# design.net
KiCad netlist of a schematic drawn in Altium Designer
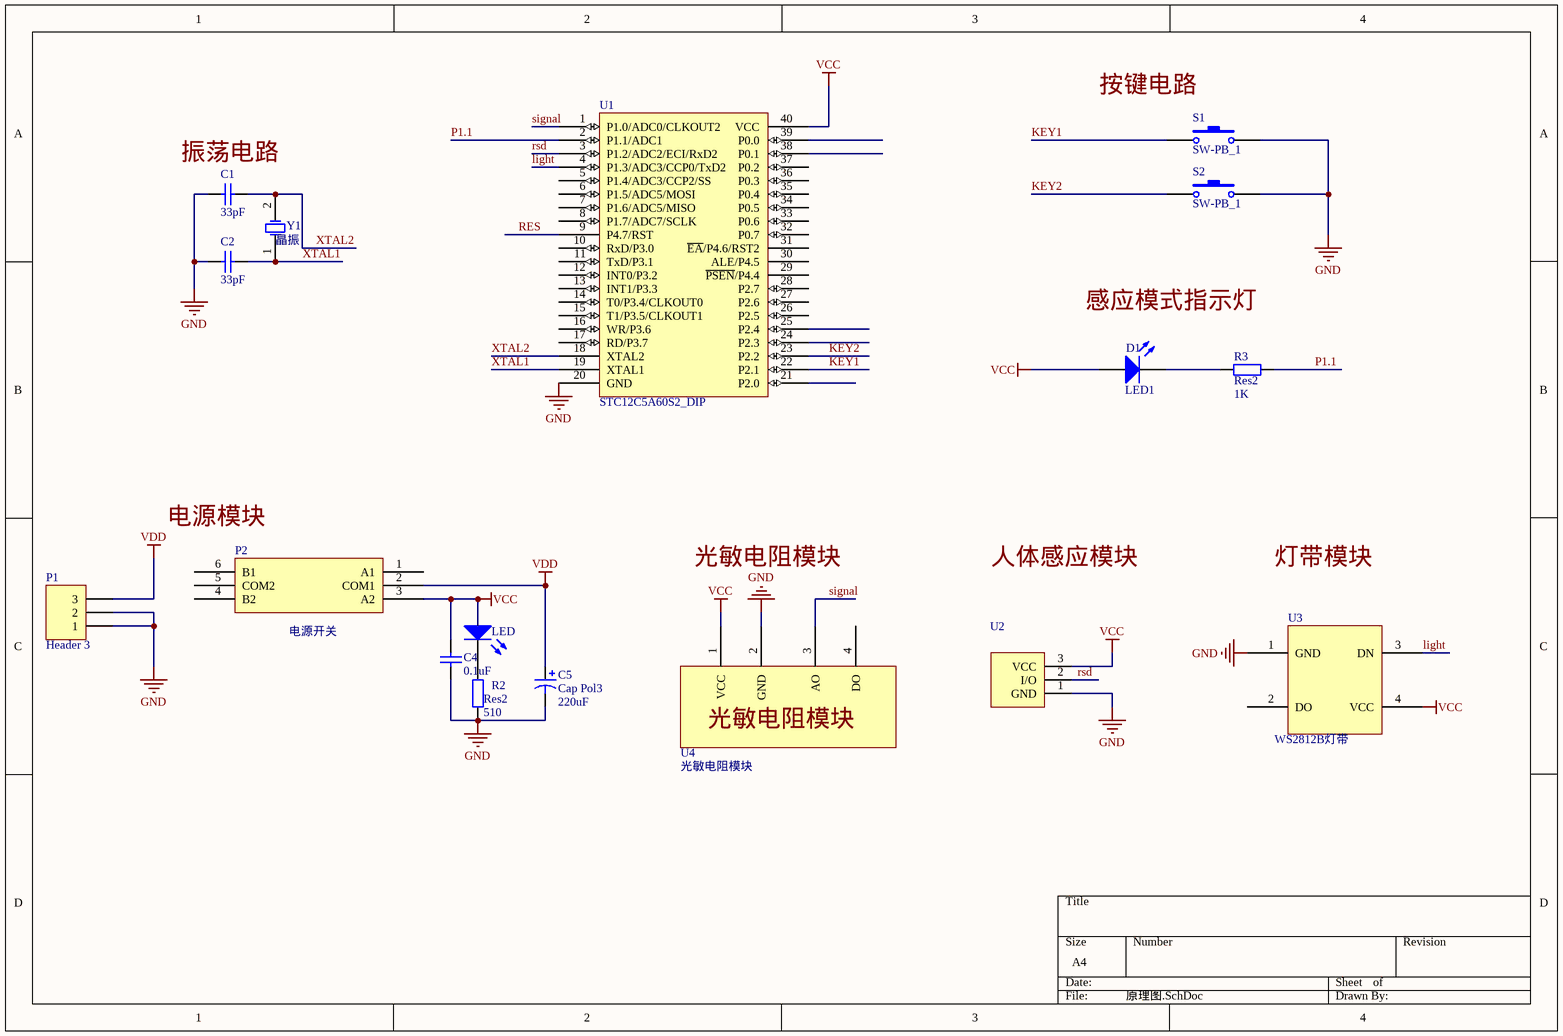
[diagram p0: 原理图.SchDoc]

(export (version "E")
  (design (tool "Eeschema 10.0.6"))
  (components
    (comp (ref "C1")
      (value "33pF")
      (footprint "Capacitor-Disk-Middle")
      (description "CBB聚乙烯薄膜电容")
      (fields
        (field (name "VOLTAGE") "63V")
        (field (name "Comment") "Cap Nicklon")
        (field (name "PUBLISHER") "Altium Limited")
      )
      (libsource (lib "02 Miscellaneous_Devices_ZSF_Library") (part "Cap Nicklon"))
    )
    (comp (ref "C2")
      (value "33pF")
      (footprint "Capacitor-Disk-Middle")
      (description "CBB聚乙烯薄膜电容")
      (fields
        (field (name "VOLTAGE") "63V")
        (field (name "Comment") "Cap Nicklon")
        (field (name "PUBLISHER") "Altium Limited")
      )
      (libsource (lib "02 Miscellaneous_Devices_ZSF_Library") (part "Cap Nicklon"))
    )
    (comp (ref "C4")
      (value "0.1uF")
      (footprint "Capacitor-Disk-Middle")
      (description "CBB聚乙烯薄膜电容")
      (fields
        (field (name "VOLTAGE") "63V")
        (field (name "Comment") "Cap Nicklon")
        (field (name "PUBLISHER") "Altium Limited")
      )
      (libsource (lib "02 Miscellaneous_Devices_ZSF_Library") (part "Cap Nicklon"))
    )
    (comp (ref "C5")
      (value "Cap Pol3")
      (footprint "ED4")
      (description "Polarized Capacitor (Surface Mount)")
      (fields (field (name "ALTIUM_VALUE") "220uF") (field (name "PUBLISHER") "Altium Limited"))
      (libsource (lib "Miscellaneous Devices") (part "Cap Pol3"))
    )
    (comp (ref "D1")
      (value "LED1")
      (footprint "CLED3216-1206")
      (description "Typical INFRARED GaAs LED")
      (fields (field (name "PUBLISHER") "Altium Limited"))
      (libsource (lib "Miscellaneous Devices") (part "LED0"))
    )
    (comp (ref "LED")
      (value "LED Chip")
      (footprint "CLED3216-1206")
      (description "Typical Chip LED")
      (fields (field (name "PUBLISHER") "Altium Limited"))
      (libsource (lib "03-EButterflyIntegratedLibrary") (part "LED Chip"))
    )
    (comp (ref "P1")
      (value "Header 3")
      (footprint "HT396K-3")
      (description "Header, 3-Pin")
      (fields (field (name "PUBLISHER") "Altium Limited"))
      (libsource (lib "01 Connect_IntegratedLibrary") (part "Header 3"))
    )
    (comp (ref "P2") (value "电源开关") (footprint "HDR2X3_CEN") (libsource (lib "stc12") (part "电源开关")))
    (comp (ref "R2")
      (value "Res2")
      (footprint "AXIAL-0.4")
      (description "Resistor")
      (fields (field (name "ALTIUM_VALUE") "510") (field (name "PUBLISHER") "Altium Limited"))
      (libsource (lib "") (part "Res2_1"))
    )
    (comp (ref "R3")
      (value "Res2")
      (footprint "AXIAL-0.4")
      (description "Resistor")
      (fields (field (name "ALTIUM_VALUE") "1K") (field (name "PUBLISHER") "Altium Limited"))
      (libsource (lib "Miscellaneous Devices") (part "Res2"))
    )
    (comp (ref "S1")
      (value "SW-PB_1")
      (footprint "BUTTON_6*6")
      (description "Switch")
      (fields (field (name "PUBLISHER") "Altium Limited"))
      (libsource (lib "02 Miscellaneous_Devices_ZSF_Library") (part "SW-PB_1"))
    )
    (comp (ref "S2")
      (value "SW-PB_1")
      (footprint "BUTTON_6*6")
      (description "Switch")
      (fields (field (name "PUBLISHER") "Altium Limited"))
      (libsource (lib "02 Miscellaneous_Devices_ZSF_Library") (part "SW-PB_1"))
    )
    (comp (ref "U1")
      (value "STC12C5A60S2_DIP")
      (footprint "dip40 - 紧缩座")
      (libsource (lib "02 Miscellaneous_Devices_ZSF_Library") (part "STC12C5A60S2_DIP"))
    )
    (comp (ref "U2") (value "人体感应模块") (footprint "人体感应模块") (libsource (lib "常用集成库(1)") (part "DS18B20")))
    (comp (ref "U3") (value "WS2812B灯带") (footprint "灯带模块") (libsource (lib "stc12") (part "WS2812B")))
    (comp (ref "U4") (value "光敏电阻模块") (footprint "光敏电阻模块") (libsource (lib "stc12") (part "光敏电阻模块")))
    (comp (ref "Y1")
      (value "晶振")
      (footprint "cry卧式")
      (description "直插晶振11.05292/12/16/24/MHz")
      (libsource (lib "02 Miscellaneous_Devices_ZSF_Library") (part "Crystal 11.05292/12/16/24/MHz"))
    )
  )
  (nets
    (net (code "1") (name "/KEY1") (class "Default")
      (node (ref "S1") (pin "1") (pinfunction "1_1") (pintype "passive"))
      (node (ref "U1") (pin "22") (pinfunction "P2.1_22") (pintype "bidirectional"))
    )
    (net (code "2") (name "/KEY2") (class "Default")
      (node (ref "S2") (pin "1") (pinfunction "1_1") (pintype "passive"))
      (node (ref "U1") (pin "23") (pinfunction "P2.2_23") (pintype "bidirectional"))
    )
    (net (code "3") (name "/P1.1") (class "Default")
      (node (ref "R3") (pin "2") (pinfunction "2_2") (pintype "passive"))
      (node (ref "U1") (pin "2") (pinfunction "P1.1/ADC1_2") (pintype "bidirectional"))
    )
    (net (code "4") (name "/RES") (class "Default")
      (node (ref "U1") (pin "9") (pinfunction "P4.7/RST_9") (pintype "passive"))
    )
    (net (code "5") (name "/XTAL1") (class "Default")
      (node (ref "C2") (pin "2") (pinfunction "2_2") (pintype "passive"))
      (node (ref "U1") (pin "19") (pinfunction "XTAL1_19") (pintype "passive"))
      (node (ref "Y1") (pin "1") (pinfunction "OSC1_1") (pintype "passive"))
    )
    (net (code "6") (name "/XTAL2") (class "Default")
      (node (ref "C1") (pin "2") (pinfunction "2_2") (pintype "passive"))
      (node (ref "U1") (pin "18") (pinfunction "XTAL2_18") (pintype "passive"))
      (node (ref "Y1") (pin "2") (pinfunction "OSC2_2") (pintype "passive"))
    )
    (net (code "7") (name "/light") (class "Default")
      (node (ref "U1") (pin "4") (pinfunction "P1.3/ADC3/CCP0/TxD2_4") (pintype "bidirectional"))
      (node (ref "U3") (pin "3") (pinfunction "DN_3") (pintype "passive"))
    )
    (net (code "8") (name "/rsd") (class "Default")
      (node (ref "U1") (pin "3") (pinfunction "P1.2/ADC2/ECI/RxD2_3") (pintype "bidirectional"))
      (node (ref "U2") (pin "2") (pinfunction "I/O_2") (pintype "passive"))
    )
    (net (code "9") (name "/signal") (class "Default")
      (node (ref "U1") (pin "1") (pinfunction "P1.0/ADC0/CLKOUT2_1") (pintype "bidirectional"))
      (node (ref "U4") (pin "3") (pinfunction "AO_3") (pintype "passive"))
    )
    (net (code "10") (name "GND") (class "Default")
      (node (ref "C1") (pin "1") (pinfunction "1_1") (pintype "passive"))
      (node (ref "C2") (pin "1") (pinfunction "1_1") (pintype "passive"))
      (node (ref "C4") (pin "1") (pinfunction "1_1") (pintype "passive"))
      (node (ref "C5") (pin "2") (pinfunction "2_2") (pintype "passive"))
      (node (ref "P1") (pin "1") (pinfunction "1_1") (pintype "passive"))
      (node (ref "P1") (pin "2") (pinfunction "2_2") (pintype "passive"))
      (node (ref "R2") (pin "1") (pinfunction "1_1") (pintype "passive"))
      (node (ref "S1") (pin "2") (pinfunction "2_2") (pintype "passive"))
      (node (ref "S2") (pin "2") (pinfunction "2_2") (pintype "passive"))
      (node (ref "U1") (pin "20") (pinfunction "GND_20") (pintype "power_in"))
      (node (ref "U2") (pin "1") (pinfunction "GND_1") (pintype "passive"))
      (node (ref "U3") (pin "1") (pinfunction "GND_1") (pintype "passive"))
      (node (ref "U4") (pin "2") (pinfunction "GND_2") (pintype "passive"))
    )
    (net (code "11") (name "Net-(D1-K)") (class "Default")
      (node (ref "D1") (pin "2") (pinfunction "K_2") (pintype "passive"))
      (node (ref "R3") (pin "1") (pinfunction "1_1") (pintype "passive"))
    )
    (net (code "12") (name "Net-(LED-K)") (class "Default")
      (node (ref "LED") (pin "2") (pinfunction "K_2") (pintype "passive"))
      (node (ref "R2") (pin "2") (pinfunction "2_2") (pintype "passive"))
    )
    (net (code "13") (name "VCC") (class "Default")
      (node (ref "C4") (pin "2") (pinfunction "2_2") (pintype "passive"))
      (node (ref "D1") (pin "1") (pinfunction "A_1") (pintype "passive"))
      (node (ref "LED") (pin "1") (pinfunction "A_1") (pintype "passive"))
      (node (ref "P2") (pin "3") (pinfunction "A2_3") (pintype "passive"))
      (node (ref "U1") (pin "40") (pinfunction "VCC_40") (pintype "power_in"))
      (node (ref "U2") (pin "3") (pinfunction "VCC_3") (pintype "passive"))
      (node (ref "U3") (pin "4") (pinfunction "VCC_4") (pintype "passive"))
      (node (ref "U4") (pin "1") (pinfunction "VCC_1") (pintype "passive"))
    )
    (net (code "14") (name "VDD") (class "Default")
      (node (ref "C5") (pin "1") (pinfunction "1_1") (pintype "passive"))
      (node (ref "P1") (pin "3") (pinfunction "3_3") (pintype "passive"))
      (node (ref "P2") (pin "2") (pinfunction "COM1_2") (pintype "passive"))
    )
    (net (code "15") (name "unconnected-(P2-A1-Pad1)") (class "Default")
      (node (ref "P2") (pin "1") (pinfunction "A1_1") (pintype "passive"))
    )
    (net (code "16") (name "unconnected-(P2-B1-Pad6)") (class "Default")
      (node (ref "P2") (pin "6") (pinfunction "B1_6") (pintype "passive"))
    )
    (net (code "17") (name "unconnected-(P2-B2-Pad4)") (class "Default")
      (node (ref "P2") (pin "4") (pinfunction "B2_4") (pintype "passive"))
    )
    (net (code "18") (name "unconnected-(P2-COM2-Pad5)") (class "Default")
      (node (ref "P2") (pin "5") (pinfunction "COM2_5") (pintype "passive"))
    )
    (net (code "19") (name "unconnected-(U1-ALE{slash}P4.5-Pad30)") (class "Default")
      (node (ref "U1") (pin "30") (pinfunction "ALE/P4.5_30") (pintype "passive"))
    )
    (net (code "20") (name "unconnected-(U1-INT0{slash}P3.2-Pad12)") (class "Default")
      (node (ref "U1") (pin "12") (pinfunction "INT0/P3.2_12") (pintype "bidirectional"))
    )
    (net (code "21") (name "unconnected-(U1-INT1{slash}P3.3-Pad13)") (class "Default")
      (node (ref "U1") (pin "13") (pinfunction "INT1/P3.3_13") (pintype "bidirectional"))
    )
    (net (code "22") (name "unconnected-(U1-P0.0-Pad39)") (class "Default")
      (node (ref "U1") (pin "39") (pinfunction "P0.0_39") (pintype "bidirectional"))
    )
    (net (code "23") (name "unconnected-(U1-P0.1-Pad38)") (class "Default")
      (node (ref "U1") (pin "38") (pinfunction "P0.1_38") (pintype "bidirectional"))
    )
    (net (code "24") (name "unconnected-(U1-P0.2-Pad37)") (class "Default")
      (node (ref "U1") (pin "37") (pinfunction "P0.2_37") (pintype "bidirectional"))
    )
    (net (code "25") (name "unconnected-(U1-P0.3-Pad36)") (class "Default")
      (node (ref "U1") (pin "36") (pinfunction "P0.3_36") (pintype "bidirectional"))
    )
    (net (code "26") (name "unconnected-(U1-P0.4-Pad35)") (class "Default")
      (node (ref "U1") (pin "35") (pinfunction "P0.4_35") (pintype "bidirectional"))
    )
    (net (code "27") (name "unconnected-(U1-P0.5-Pad34)") (class "Default")
      (node (ref "U1") (pin "34") (pinfunction "P0.5_34") (pintype "bidirectional"))
    )
    (net (code "28") (name "unconnected-(U1-P0.6-Pad33)") (class "Default")
      (node (ref "U1") (pin "33") (pinfunction "P0.6_33") (pintype "bidirectional"))
    )
    (net (code "29") (name "unconnected-(U1-P0.7-Pad32)") (class "Default")
      (node (ref "U1") (pin "32") (pinfunction "P0.7_32") (pintype "bidirectional"))
    )
    (net (code "30") (name "unconnected-(U1-P1.4{slash}ADC3{slash}CCP2{slash}SS-Pad5)") (class "Default")
      (node (ref "U1") (pin "5") (pinfunction "P1.4/ADC3/CCP2/SS_5") (pintype "bidirectional"))
    )
    (net (code "31") (name "unconnected-(U1-P1.5{slash}ADC5{slash}MOSI-Pad6)") (class "Default")
      (node (ref "U1") (pin "6") (pinfunction "P1.5/ADC5/MOSI_6") (pintype "bidirectional"))
    )
    (net (code "32") (name "unconnected-(U1-P1.6{slash}ADC5{slash}MISO-Pad7)") (class "Default")
      (node (ref "U1") (pin "7") (pinfunction "P1.6/ADC5/MISO_7") (pintype "bidirectional"))
    )
    (net (code "33") (name "unconnected-(U1-P1.7{slash}ADC7{slash}SCLK-Pad8)") (class "Default")
      (node (ref "U1") (pin "8") (pinfunction "P1.7/ADC7/SCLK_8") (pintype "bidirectional"))
    )
    (net (code "34") (name "unconnected-(U1-P2.0-Pad21)") (class "Default")
      (node (ref "U1") (pin "21") (pinfunction "P2.0_21") (pintype "bidirectional"))
    )
    (net (code "35") (name "unconnected-(U1-P2.3-Pad24)") (class "Default")
      (node (ref "U1") (pin "24") (pinfunction "P2.3_24") (pintype "bidirectional"))
    )
    (net (code "36") (name "unconnected-(U1-P2.4-Pad25)") (class "Default")
      (node (ref "U1") (pin "25") (pinfunction "P2.4_25") (pintype "bidirectional"))
    )
    (net (code "37") (name "unconnected-(U1-P2.5-Pad26)") (class "Default")
      (node (ref "U1") (pin "26") (pinfunction "P2.5_26") (pintype "bidirectional"))
    )
    (net (code "38") (name "unconnected-(U1-P2.6-Pad27)") (class "Default")
      (node (ref "U1") (pin "27") (pinfunction "P2.6_27") (pintype "bidirectional"))
    )
    (net (code "39") (name "unconnected-(U1-P2.7-Pad28)") (class "Default")
      (node (ref "U1") (pin "28") (pinfunction "P2.7_28") (pintype "bidirectional"))
    )
    (net (code "40") (name "unconnected-(U1-RD{slash}P3.7-Pad17)") (class "Default")
      (node (ref "U1") (pin "17") (pinfunction "RD/P3.7_17") (pintype "bidirectional"))
    )
    (net (code "41") (name "unconnected-(U1-RxD{slash}P3.0-Pad10)") (class "Default")
      (node (ref "U1") (pin "10") (pinfunction "RxD/P3.0_10") (pintype "bidirectional"))
    )
    (net (code "42") (name "unconnected-(U1-T0{slash}P3.4{slash}CLKOUT0-Pad14)") (class "Default")
      (node (ref "U1") (pin "14") (pinfunction "T0/P3.4/CLKOUT0_14") (pintype "bidirectional"))
    )
    (net (code "43") (name "unconnected-(U1-T1{slash}P3.5{slash}CLKOUT1-Pad15)") (class "Default")
      (node (ref "U1") (pin "15") (pinfunction "T1/P3.5/CLKOUT1_15") (pintype "bidirectional"))
    )
    (net (code "44") (name "unconnected-(U1-TxD{slash}P3.1-Pad11)") (class "Default")
      (node (ref "U1") (pin "11") (pinfunction "TxD/P3.1_11") (pintype "bidirectional"))
    )
    (net (code "45") (name "unconnected-(U1-WR{slash}P3.6-Pad16)") (class "Default")
      (node (ref "U1") (pin "16") (pinfunction "WR/P3.6_16") (pintype "bidirectional"))
    )
    (net (code "46") (name "unconnected-(U1-~{EA}{slash}P4.6{slash}RST2-Pad31)") (class "Default")
      (node (ref "U1") (pin "31") (pinfunction "~{EA}/P4.6/RST2_31") (pintype "passive"))
    )
    (net (code "47") (name "unconnected-(U1-~{PSEN}{slash}P4.4-Pad29)") (class "Default")
      (node (ref "U1") (pin "29") (pinfunction "~{PSEN}/P4.4_29") (pintype "passive"))
    )
    (net (code "48") (name "unconnected-(U3-DO-Pad2)") (class "Default")
      (node (ref "U3") (pin "2") (pinfunction "DO_2") (pintype "passive"))
    )
    (net (code "49") (name "unconnected-(U4-DO-Pad4)") (class "Default")
      (node (ref "U4") (pin "4") (pinfunction "DO_4") (pintype "passive"))
    )
  )
)
